# Lilypad_Arduino_USB.net
KiCad netlist of a schematic drawn in EAGLE
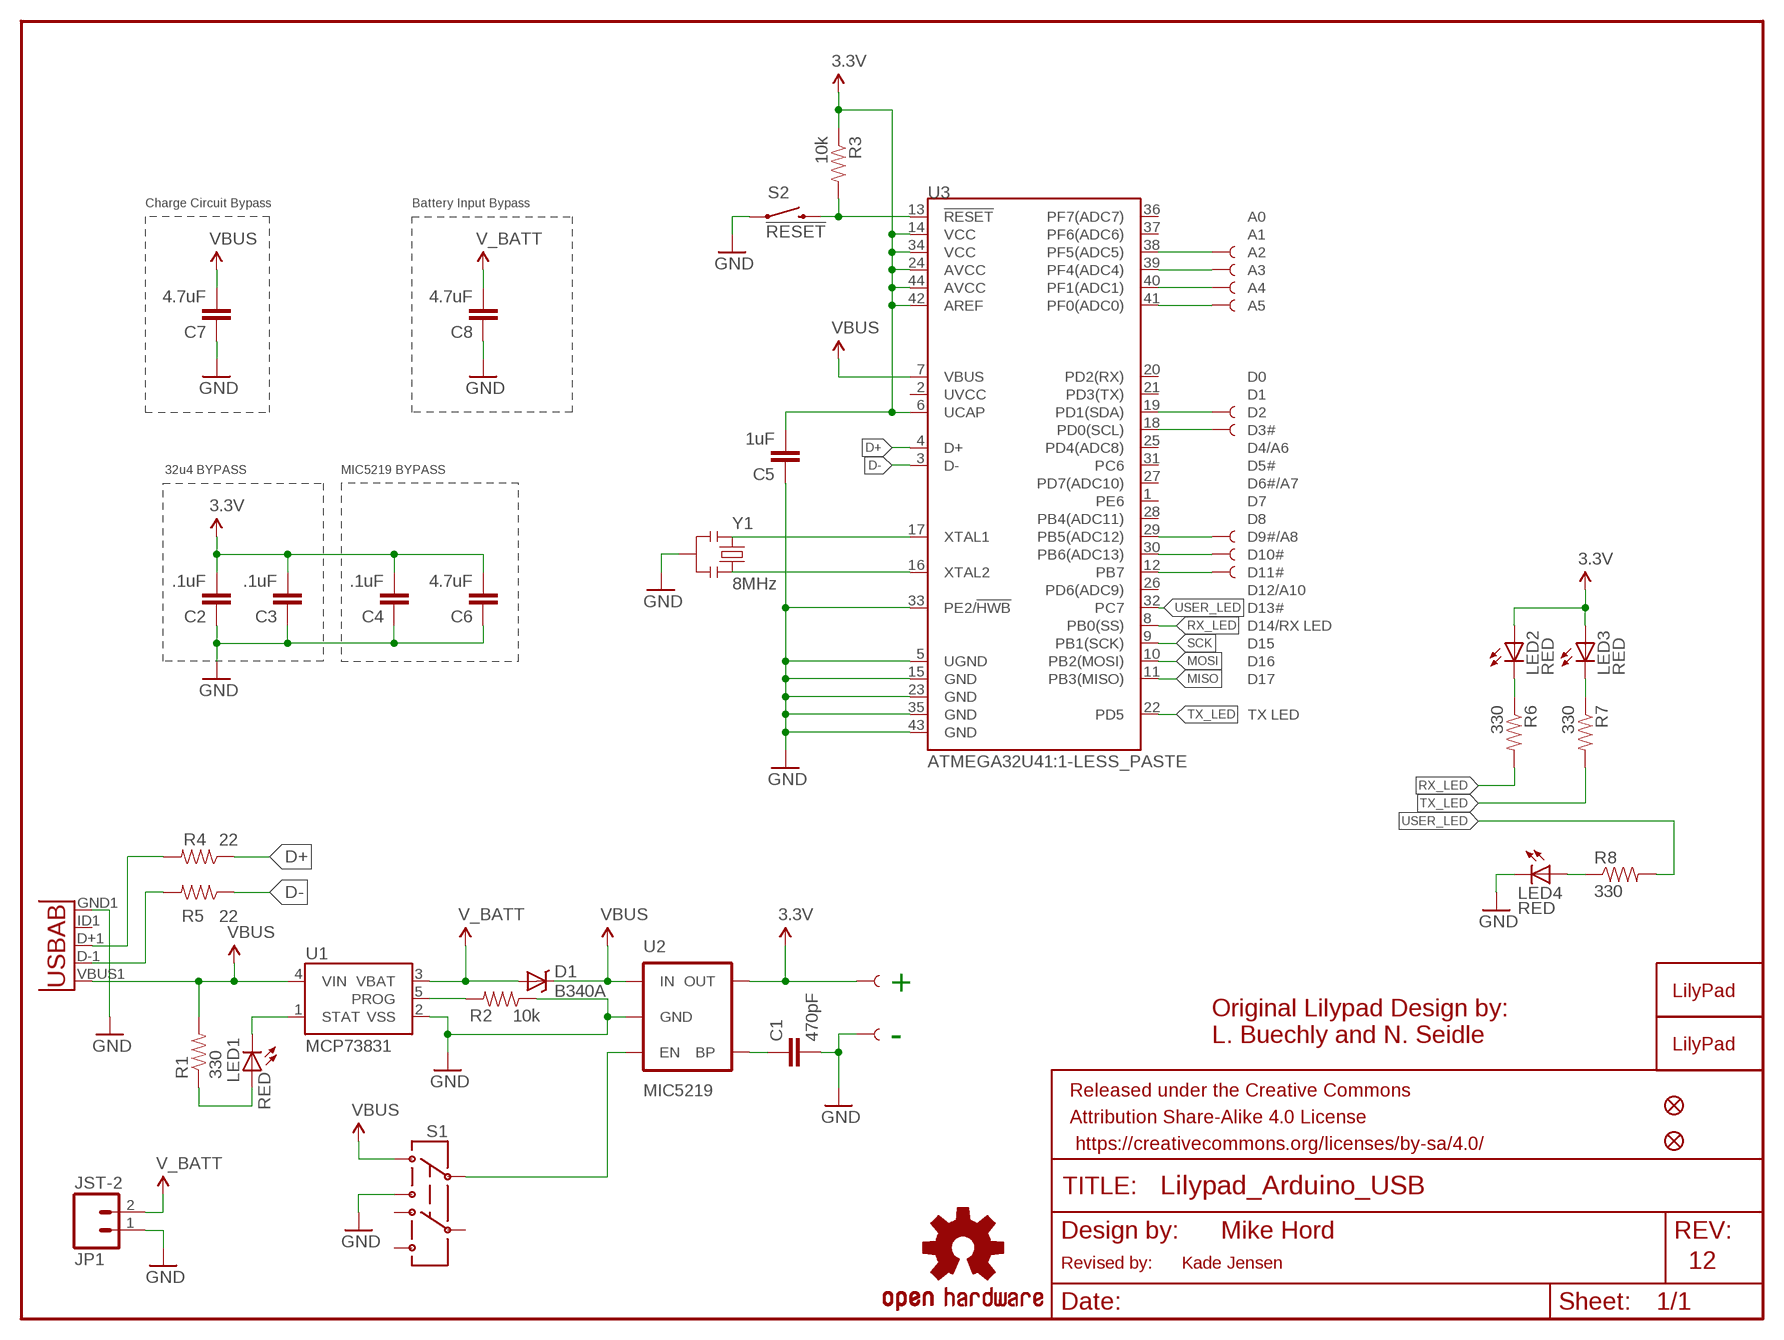
[diagram p0: schematic, sheet 1]

(export (version "E")
  (design (tool "Eeschema 10.0.6"))
  (components
    (comp (ref "+")
      (value "SEWTAP9")
      (footprint "eagle-import:PETAL-LONG-1-2SIDE")
      (fields (field (name "NO_PART") "1"))
      (libsource (lib "eagle-import") (part "SEWTAP9"))
    )
    (comp (ref "-")
      (value "SEWTAP9")
      (footprint "eagle-import:PETAL-LONG-1-2SIDE")
      (fields (field (name "NO_PART") "1"))
      (libsource (lib "eagle-import") (part "SEWTAP9"))
    )
    (comp (ref "A2")
      (value "SEWTAP9")
      (footprint "eagle-import:PETAL-LONG-1-2SIDE")
      (fields (field (name "NO_PART") "1"))
      (libsource (lib "eagle-import") (part "SEWTAP9"))
    )
    (comp (ref "A3")
      (value "SEWTAP9")
      (footprint "eagle-import:PETAL-LONG-1-2SIDE")
      (fields (field (name "NO_PART") "1"))
      (libsource (lib "eagle-import") (part "SEWTAP9"))
    )
    (comp (ref "A4")
      (value "SEWTAP9")
      (footprint "eagle-import:PETAL-LONG-1-2SIDE")
      (fields (field (name "NO_PART") "1"))
      (libsource (lib "eagle-import") (part "SEWTAP9"))
    )
    (comp (ref "A5")
      (value "SEWTAP9")
      (footprint "eagle-import:PETAL-LONG-1-2SIDE")
      (fields (field (name "NO_PART") "1"))
      (libsource (lib "eagle-import") (part "SEWTAP9"))
    )
    (comp (ref "C1")
      (value "470pF")
      (footprint "eagle-import:0603-CAP")
      (libsource (lib "eagle-import") (part "CAP0603-CAP"))
    )
    (comp (ref "C2")
      (value ".1uF")
      (footprint "eagle-import:0603-CAP")
      (libsource (lib "eagle-import") (part "CAP0603-CAP"))
    )
    (comp (ref "C3")
      (value ".1uF")
      (footprint "eagle-import:0603-CAP")
      (libsource (lib "eagle-import") (part "CAP0603-CAP"))
    )
    (comp (ref "C4")
      (value ".1uF")
      (footprint "eagle-import:0603-CAP")
      (libsource (lib "eagle-import") (part "CAP0603-CAP"))
    )
    (comp (ref "C5")
      (value "1uF")
      (footprint "eagle-import:0603-CAP")
      (libsource (lib "eagle-import") (part "CAP0603-CAP"))
    )
    (comp (ref "C6")
      (value "4.7uF")
      (footprint "eagle-import:0603-CAP")
      (libsource (lib "eagle-import") (part "CAP0603-CAP"))
    )
    (comp (ref "C7")
      (value "4.7uF")
      (footprint "eagle-import:1206")
      (libsource (lib "eagle-import") (part "CAP1206"))
    )
    (comp (ref "C8")
      (value "4.7uF")
      (footprint "eagle-import:1206")
      (libsource (lib "eagle-import") (part "CAP1206"))
    )
    (comp (ref "D1")
      (value "B340A")
      (footprint "eagle-import:SMA-DIODE")
      (libsource (lib "eagle-import") (part "DIODE-SCHOTTKY-B340A"))
    )
    (comp (ref "D5")
      (value "SEWTAP9")
      (footprint "eagle-import:PETAL-LONG-1-2SIDE")
      (fields (field (name "NO_PART") "1"))
      (libsource (lib "eagle-import") (part "SEWTAP9"))
    )
    (comp (ref "D6")
      (value "SEWTAP9")
      (footprint "eagle-import:PETAL-LONG-1-2SIDE")
      (fields (field (name "NO_PART") "1"))
      (libsource (lib "eagle-import") (part "SEWTAP9"))
    )
    (comp (ref "D9")
      (value "SEWTAP9")
      (footprint "eagle-import:PETAL-LONG-1-2SIDE")
      (fields (field (name "NO_PART") "1"))
      (libsource (lib "eagle-import") (part "SEWTAP9"))
    )
    (comp (ref "D10")
      (value "SEWTAP9")
      (footprint "eagle-import:PETAL-LONG-1-2SIDE")
      (fields (field (name "NO_PART") "1"))
      (libsource (lib "eagle-import") (part "SEWTAP9"))
    )
    (comp (ref "D11")
      (value "SEWTAP9")
      (footprint "eagle-import:PETAL-LONG-1-2SIDE")
      (fields (field (name "NO_PART") "1"))
      (libsource (lib "eagle-import") (part "SEWTAP9"))
    )
    (comp (ref "FRAME1")
      (value "FRAME-LETTER")
      (footprint "eagle-import:CREATIVE_COMMONS")
      (libsource (lib "eagle-import") (part "FRAME-LETTER"))
    )
    (comp (ref "JP1")
      (value "JST-2")
      (footprint "eagle-import:JST-2-SMD")
      (fields (field (name "PROD_ID") "CONN-08352"))
      (libsource (lib "eagle-import") (part "M02-JST-2MM-SMT"))
    )
    (comp (ref "JP2")
      (value "FIDUCIAL1X2")
      (footprint "eagle-import:FIDUCIAL-1X2")
      (libsource (lib "eagle-import") (part "FIDUCIAL1X2"))
    )
    (comp (ref "JP3")
      (value "FIDUCIAL1X2")
      (footprint "eagle-import:FIDUCIAL-1X2")
      (libsource (lib "eagle-import") (part "FIDUCIAL1X2"))
    )
    (comp (ref "LED1")
      (value "RED")
      (footprint "eagle-import:LED-0603")
      (libsource (lib "eagle-import") (part "LED0603"))
    )
    (comp (ref "LED2")
      (value "RED")
      (footprint "eagle-import:LED-0603")
      (libsource (lib "eagle-import") (part "LED0603"))
    )
    (comp (ref "LED3")
      (value "RED")
      (footprint "eagle-import:LED-0603")
      (libsource (lib "eagle-import") (part "LED0603"))
    )
    (comp (ref "LED4")
      (value "RED")
      (footprint "eagle-import:LED-0603")
      (libsource (lib "eagle-import") (part "LED0603"))
    )
    (comp (ref "R1")
      (value "330")
      (footprint "eagle-import:0603-RES")
      (libsource (lib "eagle-import") (part "RESISTOR0603-RES"))
    )
    (comp (ref "R2")
      (value "10k")
      (footprint "eagle-import:0603-RES")
      (libsource (lib "eagle-import") (part "SparkFun-Resistors_RESISTOR0603-RES"))
    )
    (comp (ref "R3")
      (value "10k")
      (footprint "eagle-import:0603-RES")
      (libsource (lib "eagle-import") (part "SparkFun-Resistors_RESISTOR0603-RES"))
    )
    (comp (ref "R4")
      (value "22")
      (footprint "eagle-import:0603-RES")
      (libsource (lib "eagle-import") (part "SparkFun-Resistors_RESISTOR0603-RES"))
    )
    (comp (ref "R5")
      (value "22")
      (footprint "eagle-import:0603-RES")
      (libsource (lib "eagle-import") (part "SparkFun-Resistors_RESISTOR0603-RES"))
    )
    (comp (ref "R6")
      (value "330")
      (footprint "eagle-import:0603-RES")
      (libsource (lib "eagle-import") (part "SparkFun-Resistors_RESISTOR0603-RES"))
    )
    (comp (ref "R7")
      (value "330")
      (footprint "eagle-import:0603-RES")
      (libsource (lib "eagle-import") (part "RESISTOR0603-RES"))
    )
    (comp (ref "R8")
      (value "330")
      (footprint "eagle-import:0603-RES")
      (libsource (lib "eagle-import") (part "RESISTOR0603-RES"))
    )
    (comp (ref "S1")
      (value "SWITCH-DPDTAYZ0202")
      (footprint "eagle-import:AYZ0202")
      (fields (field (name "PROD_ID") "SWCH-08179"))
      (libsource (lib "eagle-import") (part "SWITCH-DPDTAYZ0202"))
    )
    (comp (ref "S2")
      (value "!RESET")
      (footprint "eagle-import:TACTILE_SWITCH_SMD")
      (fields (field (name "PROD_ID") "SWCH-08247"))
      (libsource (lib "eagle-import") (part "SWITCH-MOMENTARY-2SMD"))
    )
    (comp (ref "U$1")
      (value "LOGO-LPLPA")
      (footprint "eagle-import:LOGO-LPA")
      (libsource (lib "eagle-import") (part "LOGO-LPLPA"))
    )
    (comp (ref "U$5")
      (value "OSHW-LOGOM")
      (footprint "eagle-import:OSHW-LOGO-M")
      (libsource (lib "eagle-import") (part "OSHW-LOGOM"))
    )
    (comp (ref "U$13")
      (value "LOGO-LPLP")
      (footprint "eagle-import:LOGO-LILYPAD")
      (fields (field (name "NO_PART") "1"))
      (libsource (lib "eagle-import") (part "LOGO-LPLP"))
    )
    (comp (ref "U1")
      (value "MCP73831")
      (footprint "eagle-import:SOT23-5")
      (fields (field (name "PROD_ID") "IC-09995"))
      (libsource (lib "eagle-import") (part "MCP73831"))
    )
    (comp (ref "U2")
      (value "MIC5219")
      (footprint "eagle-import:SOT23-5")
      (fields (field (name "PROD_ID") "VREG-09872"))
      (libsource (lib "eagle-import") (part "V_REG_MIC52193.3V"))
    )
    (comp (ref "U3")
      (value "ATMEGA32U41:1-LESS_PASTE")
      (footprint "eagle-import:QFN-44-NOPAD_1_1-LESS_PASTE")
      (libsource (lib "eagle-import") (part "ATMEGA32U41{colon}1-LESS_PASTE"))
    )
    (comp (ref "U5")
      (value "USB-ABCONN-11794")
      (footprint "eagle-import:USB-AB-MICRO-SMD_V03")
      (libsource (lib "eagle-import") (part "USB-ABCONN-11794"))
    )
    (comp (ref "Y1")
      (value "8MHz")
      (footprint "eagle-import:RESONATOR-SMD")
      (fields (field (name "PROD_ID") "XTAL-08895"))
      (libsource (lib "eagle-import") (part "RESONATOR8MHZ"))
    )
  )
  (nets
    (net (code "1") (name "3.3V") (class "Default")
      (node (ref "+") (pin "1") (pinfunction "1_1") (pintype "bidirectional"))
      (node (ref "C2") (pin "2") (pinfunction "2_2") (pintype "passive"))
      (node (ref "C3") (pin "2") (pinfunction "2_2") (pintype "passive"))
      (node (ref "C4") (pin "2") (pinfunction "2_2") (pintype "passive"))
      (node (ref "C5") (pin "2") (pinfunction "2_2") (pintype "passive"))
      (node (ref "C6") (pin "2") (pinfunction "2_2") (pintype "passive"))
      (node (ref "LED2") (pin "A") (pinfunction "A_A") (pintype "passive"))
      (node (ref "LED3") (pin "A") (pinfunction "A_A") (pintype "passive"))
      (node (ref "R3") (pin "1") (pinfunction "1_1") (pintype "passive"))
      (node (ref "U2") (pin "5") (pinfunction "OUT_5") (pintype "passive"))
      (node (ref "U3") (pin "14") (pinfunction "VCC_14") (pintype "bidirectional"))
      (node (ref "U3") (pin "24") (pinfunction "AVCC_24") (pintype "bidirectional"))
      (node (ref "U3") (pin "34") (pinfunction "VCC_34") (pintype "bidirectional"))
      (node (ref "U3") (pin "42") (pinfunction "AREF_42") (pintype "bidirectional"))
      (node (ref "U3") (pin "44") (pinfunction "AVCC_44") (pintype "bidirectional"))
      (node (ref "U3") (pin "6") (pinfunction "UCAP_6") (pintype "bidirectional"))
    )
    (net (code "2") (name "D+") (class "Default")
      (node (ref "R4") (pin "1") (pinfunction "1_1") (pintype "passive"))
      (node (ref "U3") (pin "4") (pinfunction "D+_4") (pintype "bidirectional"))
    )
    (net (code "3") (name "D-") (class "Default")
      (node (ref "R5") (pin "1") (pinfunction "1_1") (pintype "passive"))
      (node (ref "U3") (pin "3") (pinfunction "D-_3") (pintype "bidirectional"))
    )
    (net (code "4") (name "GND") (class "Default")
      (node (ref "-") (pin "1") (pinfunction "1_1") (pintype "bidirectional"))
      (node (ref "C1") (pin "2") (pinfunction "2_2") (pintype "passive"))
      (node (ref "C2") (pin "1") (pinfunction "1_1") (pintype "passive"))
      (node (ref "C3") (pin "1") (pinfunction "1_1") (pintype "passive"))
      (node (ref "C4") (pin "1") (pinfunction "1_1") (pintype "passive"))
      (node (ref "C5") (pin "1") (pinfunction "1_1") (pintype "passive"))
      (node (ref "C6") (pin "1") (pinfunction "1_1") (pintype "passive"))
      (node (ref "C7") (pin "1") (pinfunction "1_1") (pintype "passive"))
      (node (ref "C8") (pin "1") (pinfunction "1_1") (pintype "passive"))
      (node (ref "JP1") (pin "1") (pinfunction "2_1") (pintype "passive"))
      (node (ref "LED4") (pin "C") (pinfunction "C_C") (pintype "passive"))
      (node (ref "R2") (pin "1") (pinfunction "1_1") (pintype "passive"))
      (node (ref "S1") (pin "3") (pinfunction "3_3") (pintype "bidirectional"))
      (node (ref "S2") (pin "1") (pinfunction "1_1") (pintype "passive"))
      (node (ref "U1") (pin "2") (pinfunction "VSS_2") (pintype "power_in"))
      (node (ref "U2") (pin "2") (pinfunction "GND_2") (pintype "input"))
      (node (ref "U3") (pin "15") (pinfunction "GND_15") (pintype "bidirectional"))
      (node (ref "U3") (pin "23") (pinfunction "GND_23") (pintype "bidirectional"))
      (node (ref "U3") (pin "33") (pinfunction "PE2/~{HWB}_33") (pintype "bidirectional"))
      (node (ref "U3") (pin "35") (pinfunction "GND_35") (pintype "bidirectional"))
      (node (ref "U3") (pin "43") (pinfunction "GND_43") (pintype "bidirectional"))
      (node (ref "U3") (pin "5") (pinfunction "UGND_5") (pintype "bidirectional"))
      (node (ref "U5") (pin "GND1") (pinfunction "GND_GND1") (pintype "bidirectional"))
      (node (ref "Y1") (pin "2") (pinfunction "2_2") (pintype "passive"))
    )
    (net (code "5") (name "MISO") (class "Default")
      (node (ref "U3") (pin "11") (pinfunction "PB3(MISO)_11") (pintype "bidirectional"))
    )
    (net (code "6") (name "MOSI") (class "Default")
      (node (ref "U3") (pin "10") (pinfunction "PB2(MOSI)_10") (pintype "bidirectional"))
    )
    (net (code "7") (name "Net-(LED1-PadA)") (class "Default")
      (node (ref "LED1") (pin "A") (pinfunction "A_A") (pintype "passive"))
      (node (ref "R1") (pin "1") (pinfunction "1_1") (pintype "passive"))
    )
    (net (code "8") (name "Net-(LED2-PadC)") (class "Default")
      (node (ref "LED2") (pin "C") (pinfunction "C_C") (pintype "passive"))
      (node (ref "R6") (pin "1") (pinfunction "1_1") (pintype "passive"))
    )
    (net (code "9") (name "Net-(LED3-PadC)") (class "Default")
      (node (ref "LED3") (pin "C") (pinfunction "C_C") (pintype "passive"))
      (node (ref "R7") (pin "1") (pinfunction "1_1") (pintype "passive"))
    )
    (net (code "10") (name "Net-(LED4-PadA)") (class "Default")
      (node (ref "LED4") (pin "A") (pinfunction "A_A") (pintype "passive"))
      (node (ref "R8") (pin "1") (pinfunction "1_1") (pintype "passive"))
    )
    (net (code "11") (name "Net-(S2-2)") (class "Default")
      (node (ref "R3") (pin "2") (pinfunction "2_2") (pintype "passive"))
      (node (ref "S2") (pin "3") (pinfunction "2_3") (pintype "passive"))
      (node (ref "U3") (pin "13") (pinfunction "~{RESET}_13") (pintype "bidirectional"))
    )
    (net (code "12") (name "Net-(U1-PROG)") (class "Default")
      (node (ref "R2") (pin "2") (pinfunction "2_2") (pintype "passive"))
      (node (ref "U1") (pin "5") (pinfunction "PROG_5") (pintype "input"))
    )
    (net (code "13") (name "Net-(U1-STAT)") (class "Default")
      (node (ref "LED1") (pin "C") (pinfunction "C_C") (pintype "passive"))
      (node (ref "U1") (pin "1") (pinfunction "STAT_1") (pintype "output"))
    )
    (net (code "14") (name "Net-(U2-BP)") (class "Default")
      (node (ref "C1") (pin "1") (pinfunction "1_1") (pintype "passive"))
      (node (ref "U2") (pin "4") (pinfunction "BP_4") (pintype "input"))
    )
    (net (code "15") (name "Net-(U2-EN)") (class "Default")
      (node (ref "S1") (pin "2") (pinfunction "2_2") (pintype "bidirectional"))
      (node (ref "U2") (pin "3") (pinfunction "EN_3") (pintype "input"))
    )
    (net (code "16") (name "Net-(U3-PB5(ADC12))") (class "Default")
      (node (ref "D9") (pin "1") (pinfunction "1_1") (pintype "bidirectional"))
      (node (ref "U3") (pin "29") (pinfunction "PB5(ADC12)_29") (pintype "bidirectional"))
    )
    (net (code "17") (name "Net-(U3-PB6(ADC13))") (class "Default")
      (node (ref "D10") (pin "1") (pinfunction "1_1") (pintype "bidirectional"))
      (node (ref "U3") (pin "30") (pinfunction "PB6(ADC13)_30") (pintype "bidirectional"))
    )
    (net (code "18") (name "Net-(U3-PB7)") (class "Default")
      (node (ref "D11") (pin "1") (pinfunction "1_1") (pintype "bidirectional"))
      (node (ref "U3") (pin "12") (pinfunction "PB7_12") (pintype "bidirectional"))
    )
    (net (code "19") (name "Net-(U3-PD0(SCL))") (class "Default")
      (node (ref "D6") (pin "1") (pinfunction "1_1") (pintype "bidirectional"))
      (node (ref "U3") (pin "18") (pinfunction "PD0(SCL)_18") (pintype "bidirectional"))
    )
    (net (code "20") (name "Net-(U3-PD1(SDA))") (class "Default")
      (node (ref "D5") (pin "1") (pinfunction "1_1") (pintype "bidirectional"))
      (node (ref "U3") (pin "19") (pinfunction "PD1(SDA)_19") (pintype "bidirectional"))
    )
    (net (code "21") (name "Net-(U3-PF0(ADC0))") (class "Default")
      (node (ref "A5") (pin "1") (pinfunction "1_1") (pintype "bidirectional"))
      (node (ref "U3") (pin "41") (pinfunction "PF0(ADC0)_41") (pintype "bidirectional"))
    )
    (net (code "22") (name "Net-(U3-PF1(ADC1))") (class "Default")
      (node (ref "A4") (pin "1") (pinfunction "1_1") (pintype "bidirectional"))
      (node (ref "U3") (pin "40") (pinfunction "PF1(ADC1)_40") (pintype "bidirectional"))
    )
    (net (code "23") (name "Net-(U3-PF4(ADC4))") (class "Default")
      (node (ref "A3") (pin "1") (pinfunction "1_1") (pintype "bidirectional"))
      (node (ref "U3") (pin "39") (pinfunction "PF4(ADC4)_39") (pintype "bidirectional"))
    )
    (net (code "24") (name "Net-(U3-PF5(ADC5))") (class "Default")
      (node (ref "A2") (pin "1") (pinfunction "1_1") (pintype "bidirectional"))
      (node (ref "U3") (pin "38") (pinfunction "PF5(ADC5)_38") (pintype "bidirectional"))
    )
    (net (code "25") (name "Net-(U3-XTAL1)") (class "Default")
      (node (ref "U3") (pin "17") (pinfunction "XTAL1_17") (pintype "bidirectional"))
      (node (ref "Y1") (pin "1") (pinfunction "1_1") (pintype "passive"))
    )
    (net (code "26") (name "Net-(U3-XTAL2)") (class "Default")
      (node (ref "U3") (pin "16") (pinfunction "XTAL2_16") (pintype "bidirectional"))
      (node (ref "Y1") (pin "3") (pinfunction "3_3") (pintype "passive"))
    )
    (net (code "27") (name "Net-(U5-D+)") (class "Default")
      (node (ref "R4") (pin "2") (pinfunction "2_2") (pintype "passive"))
      (node (ref "U5") (pin "D+1") (pinfunction "D+_D+1") (pintype "bidirectional"))
    )
    (net (code "28") (name "Net-(U5-D-)") (class "Default")
      (node (ref "R5") (pin "2") (pinfunction "2_2") (pintype "passive"))
      (node (ref "U5") (pin "D-1") (pinfunction "D-_D-1") (pintype "bidirectional"))
    )
    (net (code "29") (name "RX_LED") (class "Default")
      (node (ref "R6") (pin "2") (pinfunction "2_2") (pintype "passive"))
      (node (ref "U3") (pin "8") (pinfunction "PB0(SS)_8") (pintype "bidirectional"))
    )
    (net (code "30") (name "SCK") (class "Default")
      (node (ref "U3") (pin "9") (pinfunction "PB1(SCK)_9") (pintype "bidirectional"))
    )
    (net (code "31") (name "TX_LED") (class "Default")
      (node (ref "R7") (pin "2") (pinfunction "2_2") (pintype "passive"))
      (node (ref "U3") (pin "22") (pinfunction "PD5_22") (pintype "bidirectional"))
    )
    (net (code "32") (name "USER_LED") (class "Default")
      (node (ref "R8") (pin "2") (pinfunction "2_2") (pintype "passive"))
      (node (ref "U3") (pin "32") (pinfunction "PC7_32") (pintype "bidirectional"))
    )
    (net (code "33") (name "VBUS") (class "Default")
      (node (ref "C7") (pin "2") (pinfunction "2_2") (pintype "passive"))
      (node (ref "D1") (pin "C") (pinfunction "C_C") (pintype "passive"))
      (node (ref "R1") (pin "2") (pinfunction "2_2") (pintype "passive"))
      (node (ref "S1") (pin "1") (pinfunction "1_1") (pintype "bidirectional"))
      (node (ref "U1") (pin "4") (pinfunction "VIN_4") (pintype "power_in"))
      (node (ref "U2") (pin "1") (pinfunction "IN_1") (pintype "input"))
      (node (ref "U3") (pin "7") (pinfunction "VBUS_7") (pintype "bidirectional"))
      (node (ref "U5") (pin "VBUS1") (pinfunction "VBUS_VBUS1") (pintype "bidirectional"))
    )
    (net (code "34") (name "V_BATT") (class "Default")
      (node (ref "C8") (pin "2") (pinfunction "2_2") (pintype "passive"))
      (node (ref "D1") (pin "A") (pinfunction "A_A") (pintype "passive"))
      (node (ref "JP1") (pin "2") (pinfunction "1_2") (pintype "passive"))
      (node (ref "U1") (pin "3") (pinfunction "VBAT_3") (pintype "power_in"))
    )
    (net (code "35") (name "unconnected-(S1-Pad4)") (class "Default")
      (node (ref "S1") (pin "4") (pinfunction "4_4") (pintype "bidirectional"))
    )
    (net (code "36") (name "unconnected-(S1-Pad5)") (class "Default")
      (node (ref "S1") (pin "5") (pinfunction "5_5") (pintype "bidirectional"))
    )
    (net (code "37") (name "unconnected-(S1-Pad6)") (class "Default")
      (node (ref "S1") (pin "6") (pinfunction "6_6") (pintype "bidirectional"))
    )
    (net (code "38") (name "unconnected-(U3-PB4(ADC11)-Pad28)") (class "Default")
      (node (ref "U3") (pin "28") (pinfunction "PB4(ADC11)_28") (pintype "bidirectional"))
    )
    (net (code "39") (name "unconnected-(U3-PC6-Pad31)") (class "Default")
      (node (ref "U3") (pin "31") (pinfunction "PC6_31") (pintype "bidirectional"))
    )
    (net (code "40") (name "unconnected-(U3-PD2(RX)-Pad20)") (class "Default")
      (node (ref "U3") (pin "20") (pinfunction "PD2(RX)_20") (pintype "bidirectional"))
    )
    (net (code "41") (name "unconnected-(U3-PD3(TX)-Pad21)") (class "Default")
      (node (ref "U3") (pin "21") (pinfunction "PD3(TX)_21") (pintype "bidirectional"))
    )
    (net (code "42") (name "unconnected-(U3-PD4(ADC8)-Pad25)") (class "Default")
      (node (ref "U3") (pin "25") (pinfunction "PD4(ADC8)_25") (pintype "bidirectional"))
    )
    (net (code "43") (name "unconnected-(U3-PD6(ADC9)-Pad26)") (class "Default")
      (node (ref "U3") (pin "26") (pinfunction "PD6(ADC9)_26") (pintype "bidirectional"))
    )
    (net (code "44") (name "unconnected-(U3-PD7(ADC10)-Pad27)") (class "Default")
      (node (ref "U3") (pin "27") (pinfunction "PD7(ADC10)_27") (pintype "bidirectional"))
    )
    (net (code "45") (name "unconnected-(U3-PE6-Pad1)") (class "Default")
      (node (ref "U3") (pin "1") (pinfunction "PE6_1") (pintype "bidirectional"))
    )
    (net (code "46") (name "unconnected-(U3-PF6(ADC6)-Pad37)") (class "Default")
      (node (ref "U3") (pin "37") (pinfunction "PF6(ADC6)_37") (pintype "bidirectional"))
    )
    (net (code "47") (name "unconnected-(U3-PF7(ADC7)-Pad36)") (class "Default")
      (node (ref "U3") (pin "36") (pinfunction "PF7(ADC7)_36") (pintype "bidirectional"))
    )
    (net (code "48") (name "unconnected-(U3-UVCC-Pad2)") (class "Default")
      (node (ref "U3") (pin "2") (pinfunction "UVCC_2") (pintype "bidirectional"))
    )
    (net (code "49") (name "unconnected-(U5-USBID-PadID1)") (class "Default")
      (node (ref "U5") (pin "ID1") (pinfunction "USBID_ID1") (pintype "bidirectional"))
    )
  )
)
